# md_ver10_7.net
KiCad netlist of a schematic drawn in EAGLE
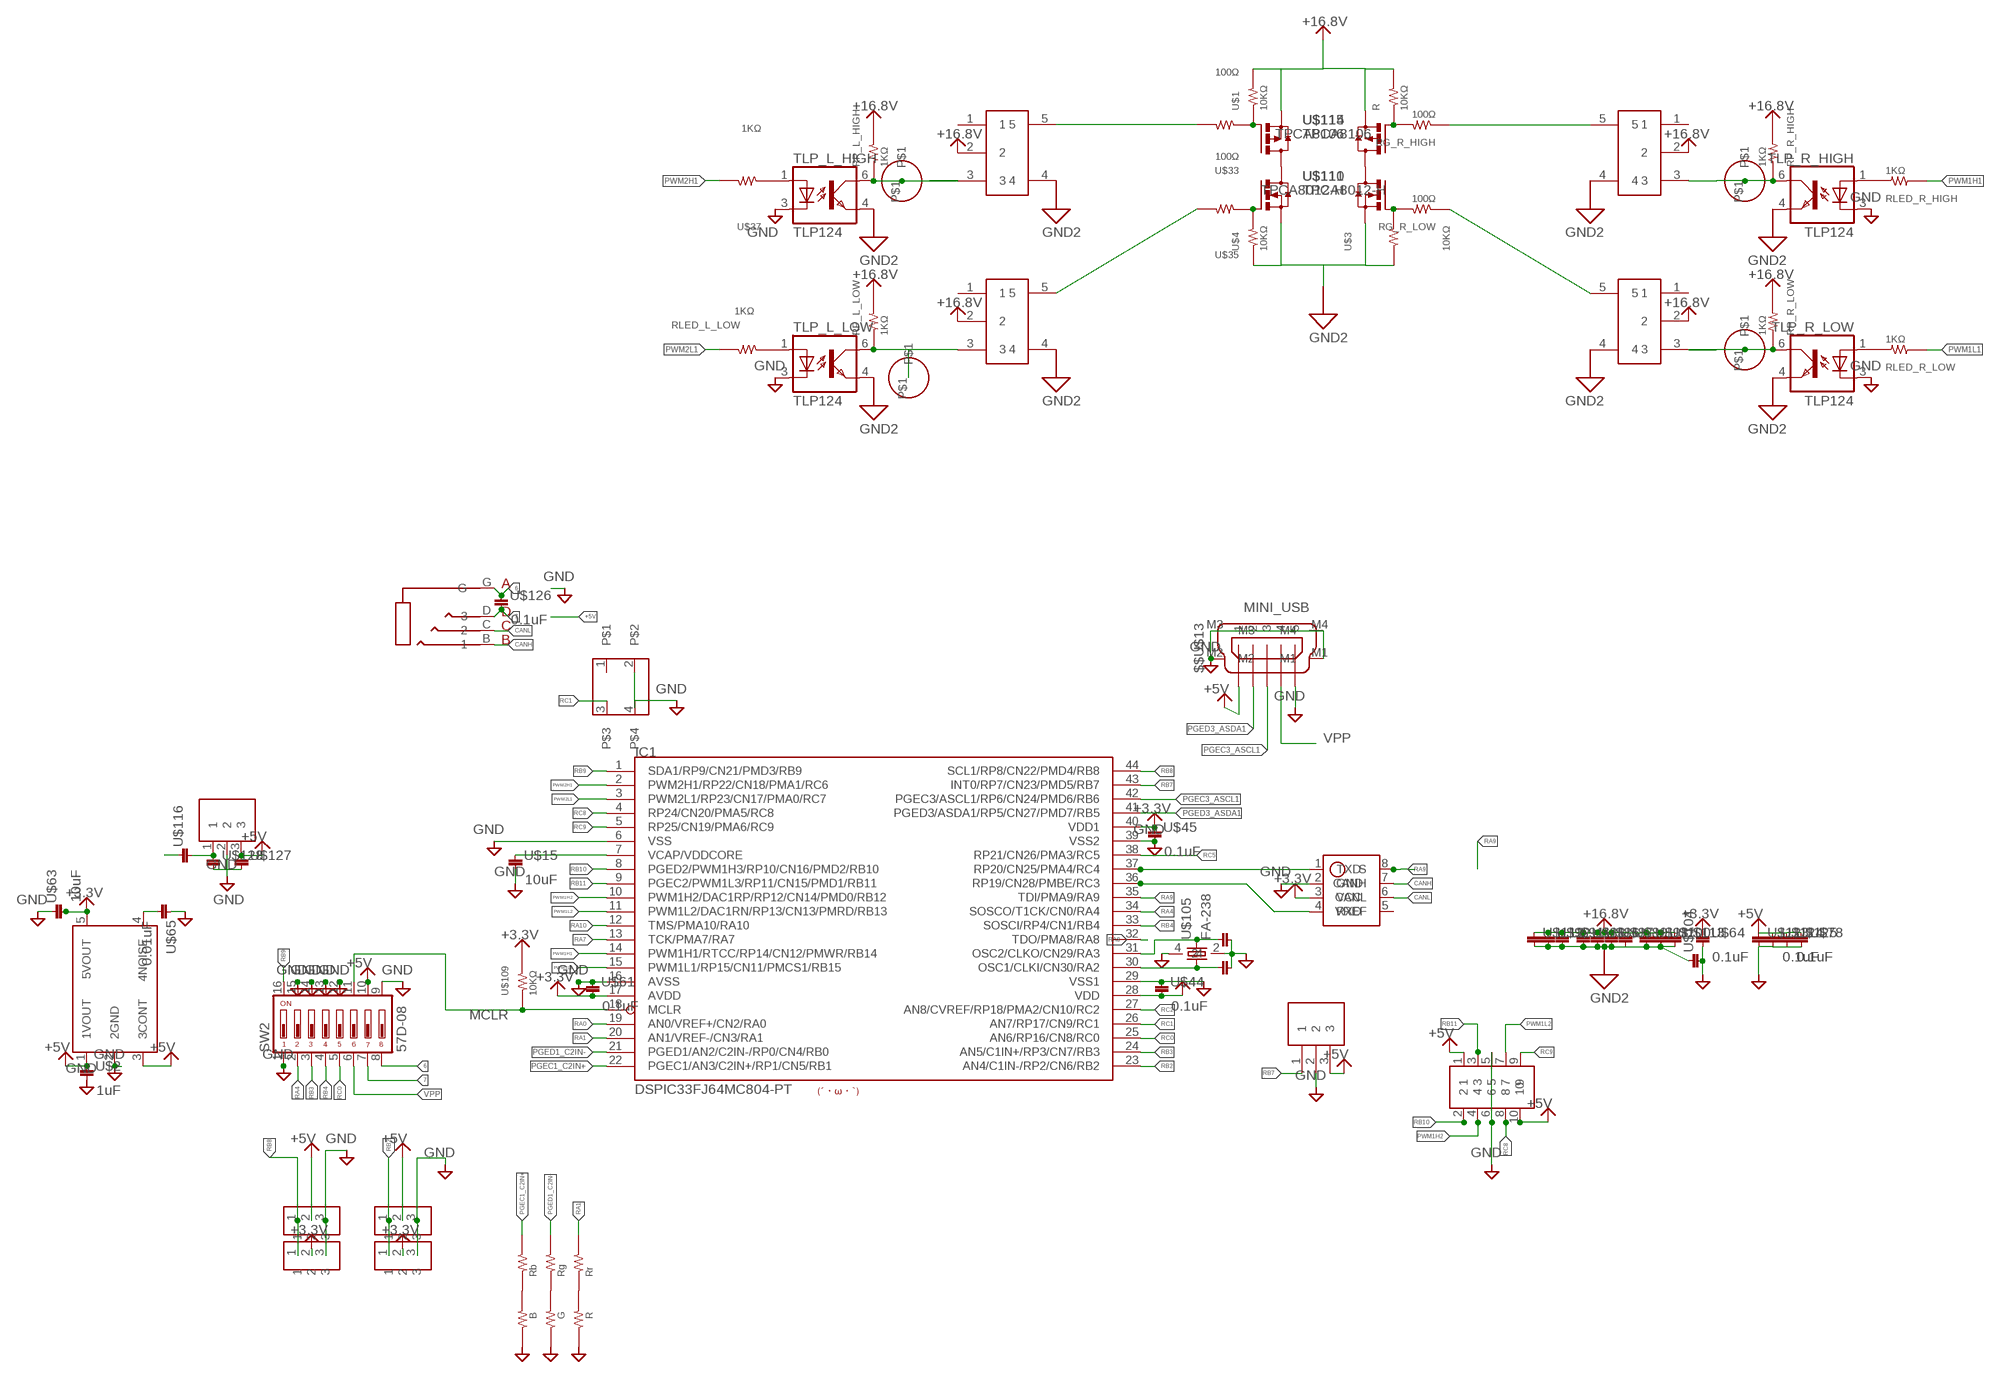
[diagram p0: schematic, sheet 1]

(export (version "E")
  (design (tool "Eeschema 10.0.6"))
  (components
    (comp (ref "$$U$5")
      (value "PAD1_4MM")
      (footprint "eagle-import:PAD1_4MM")
      (libsource (lib "eagle-import") (part "PAD1_4MM"))
    )
    (comp (ref "$$U$6")
      (value "PAD1_4MM")
      (footprint "eagle-import:PAD1_4MM")
      (libsource (lib "eagle-import") (part "PAD1_4MM"))
    )
    (comp (ref "$$U$13")
      (value "MINI_USB")
      (footprint "eagle-import:MINI_USB")
      (libsource (lib "eagle-import") (part "MINI_USB"))
    )
    (comp (ref "$$U$14")
      (value "AUDIO4")
      (footprint "eagle-import:AUDIO4_MJ")
      (libsource (lib "eagle-import") (part "AUDIO4"))
    )
    (comp (ref "$$U$102")
      (value "1608")
      (footprint "eagle-import:1608")
      (libsource (lib "eagle-import") (part "1608"))
    )
    (comp (ref "$$U$108")
      (value "Rr")
      (footprint "eagle-import:1608")
      (libsource (lib "eagle-import") (part "RESISTOR__SMD"))
    )
    (comp (ref "IC1")
      (value "DSPIC33FJ64MC804-PT")
      (footprint "eagle-import:TQFP44")
      (libsource (lib "eagle-import") (part "DSPIC33FJ64MC804-PT"))
    )
    (comp (ref "IC2")
      (value "TAR5SB")
      (footprint "eagle-import:SSOP5-P-0.95")
      (libsource (lib "eagle-import") (part "TAR5SB"))
    )
    (comp (ref "IC3")
      (value "SN65HVD1050")
      (footprint "eagle-import:SOIC8")
      (libsource (lib "eagle-import") (part "SN65HVD1050"))
    )
    (comp (ref "IC4")
      (value "ＰＬ－ＩＲＭ")
      (footprint "eagle-import:ＰＬ－ＩＲＭ")
      (libsource (lib "eagle-import") (part "ＰＬ－ＩＲＭ"))
    )
    (comp (ref "IC5")
      (value "Ｒ－７８Ｅ５．０")
      (footprint "eagle-import:Ｒ－７８Ｅ５．０")
      (libsource (lib "eagle-import") (part "Ｒ－７８Ｅ５．０"))
    )
    (comp (ref "IC_L_HIGH")
      (value "MCP1415")
      (footprint "eagle-import:SOT23-5L")
      (libsource (lib "eagle-import") (part "MCP1415"))
    )
    (comp (ref "IC_L_LOW")
      (value "MCP1415")
      (footprint "eagle-import:SOT23-5L")
      (libsource (lib "eagle-import") (part "MCP1415"))
    )
    (comp (ref "IC_R_HIGH")
      (value "MCP1415")
      (footprint "eagle-import:SOT23-5L")
      (libsource (lib "eagle-import") (part "MCP1415"))
    )
    (comp (ref "IC_R_LOW")
      (value "MCP1415")
      (footprint "eagle-import:SOT23-5L")
      (libsource (lib "eagle-import") (part "MCP1415"))
    )
    (comp (ref "R")
      (value "10KΩ")
      (footprint "eagle-import:1608")
      (libsource (lib "eagle-import") (part "RESISTOR__SMD"))
    )
    (comp (ref "RG_R_HIGH")
      (value "100Ω")
      (footprint "eagle-import:1608")
      (libsource (lib "eagle-import") (part "RESISTOR__SMD"))
    )
    (comp (ref "RG_R_LOW")
      (value "100Ω")
      (footprint "eagle-import:1608")
      (libsource (lib "eagle-import") (part "RESISTOR__SMD"))
    )
    (comp (ref "RLED_L_LOW")
      (value "1KΩ")
      (footprint "eagle-import:1608")
      (libsource (lib "eagle-import") (part "RESISTOR__SMD"))
    )
    (comp (ref "RLED_R_HIGH")
      (value "1KΩ")
      (footprint "eagle-import:1608")
      (libsource (lib "eagle-import") (part "RESISTOR__SMD"))
    )
    (comp (ref "RLED_R_LOW")
      (value "1KΩ")
      (footprint "eagle-import:1608")
      (libsource (lib "eagle-import") (part "RESISTOR__SMD"))
    )
    (comp (ref "RP_L_HIGH")
      (value "1KΩ")
      (footprint "eagle-import:1608")
      (libsource (lib "eagle-import") (part "RESISTOR__SMD"))
    )
    (comp (ref "RP_L_LOW")
      (value "1KΩ")
      (footprint "eagle-import:1608")
      (libsource (lib "eagle-import") (part "RESISTOR__SMD"))
    )
    (comp (ref "RP_R_HIGH")
      (value "1KΩ")
      (footprint "eagle-import:1608")
      (libsource (lib "eagle-import") (part "RESISTOR__SMD"))
    )
    (comp (ref "RP_R_LOW")
      (value "1KΩ")
      (footprint "eagle-import:1608")
      (libsource (lib "eagle-import") (part "RESISTOR__SMD"))
    )
    (comp (ref "SW1")
      (value "TACT")
      (footprint "eagle-import:TL1105")
      (libsource (lib "eagle-import") (part "TACT"))
    )
    (comp (ref "SW2")
      (value "57D-08")
      (footprint "eagle-import:57D")
      (libsource (lib "eagle-import") (part "57D-08"))
    )
    (comp (ref "TLP_L_HIGH")
      (value "TLP124")
      (footprint "eagle-import:11−4C1")
      (libsource (lib "eagle-import") (part "TLP124"))
    )
    (comp (ref "TLP_L_LOW")
      (value "TLP124")
      (footprint "eagle-import:11−4C1")
      (libsource (lib "eagle-import") (part "TLP124"))
    )
    (comp (ref "TLP_R_HIGH")
      (value "TLP124")
      (footprint "eagle-import:11−4C1")
      (libsource (lib "eagle-import") (part "TLP124"))
    )
    (comp (ref "TLP_R_LOW")
      (value "TLP124")
      (footprint "eagle-import:11−4C1")
      (libsource (lib "eagle-import") (part "TLP124"))
    )
    (comp (ref "U$1")
      (value "10KΩ")
      (footprint "eagle-import:1608")
      (libsource (lib "eagle-import") (part "RESISTOR__SMD"))
    )
    (comp (ref "U$2")
      (value "1uF")
      (footprint "eagle-import:1608")
      (libsource (lib "eagle-import") (part "1608"))
    )
    (comp (ref "U$3")
      (value "10KΩ")
      (footprint "eagle-import:1608")
      (libsource (lib "eagle-import") (part "RESISTOR__SMD"))
    )
    (comp (ref "U$4")
      (value "10KΩ")
      (footprint "eagle-import:1608")
      (libsource (lib "eagle-import") (part "RESISTOR__SMD"))
    )
    (comp (ref "U$7")
      (value "PAD1_4MM")
      (footprint "eagle-import:PAD1_4MM")
      (libsource (lib "eagle-import") (part "PAD1_4MM"))
    )
    (comp (ref "U$8")
      (value "PAD1_4MM")
      (footprint "eagle-import:PAD1_4MM")
      (libsource (lib "eagle-import") (part "PAD1_4MM"))
    )
    (comp (ref "U$9")
      (value "PIN_HEADER_52")
      (footprint "eagle-import:PIN_HEADER_5_2")
      (libsource (lib "eagle-import") (part "PIN_HEADER_52"))
    )
    (comp (ref "U$10")
      (value "R")
      (footprint "eagle-import:1608")
      (libsource (lib "eagle-import") (part "RESISTOR__SMD"))
    )
    (comp (ref "U$11")
      (value "G")
      (footprint "eagle-import:1608")
      (libsource (lib "eagle-import") (part "RESISTOR__SMD"))
    )
    (comp (ref "U$12")
      (value "B")
      (footprint "eagle-import:1608")
      (libsource (lib "eagle-import") (part "RESISTOR__SMD"))
    )
    (comp (ref "U$15")
      (value "10uF")
      (footprint "eagle-import:2012")
      (libsource (lib "eagle-import") (part "2012"))
    )
    (comp (ref "U$33")
      (value "100Ω")
      (footprint "eagle-import:1608")
      (libsource (lib "eagle-import") (part "RESISTOR__SMD"))
    )
    (comp (ref "U$35")
      (value "100Ω")
      (footprint "eagle-import:1608")
      (libsource (lib "eagle-import") (part "RESISTOR__SMD"))
    )
    (comp (ref "U$37")
      (value "1KΩ")
      (footprint "eagle-import:1608")
      (libsource (lib "eagle-import") (part "RESISTOR__SMD"))
    )
    (comp (ref "U$44")
      (value "0.1uF")
      (footprint "eagle-import:1608")
      (libsource (lib "eagle-import") (part "1608"))
    )
    (comp (ref "U$45")
      (value "0.1uF")
      (footprint "eagle-import:1608")
      (libsource (lib "eagle-import") (part "1608"))
    )
    (comp (ref "U$61")
      (value "0.1uF")
      (footprint "eagle-import:1608")
      (libsource (lib "eagle-import") (part "1608"))
    )
    (comp (ref "U$63")
      (value "10uF")
      (footprint "eagle-import:2012")
      (libsource (lib "eagle-import") (part "2012"))
    )
    (comp (ref "U$64")
      (value "0.1uF")
      (footprint "eagle-import:1608")
      (libsource (lib "eagle-import") (part "1608"))
    )
    (comp (ref "U$65")
      (value "0.01uF")
      (footprint "eagle-import:1608")
      (libsource (lib "eagle-import") (part "1608"))
    )
    (comp (ref "U$69")
      (value "3PIN_HALF")
      (footprint "eagle-import:3PIN_INT_HALF")
      (libsource (lib "eagle-import") (part "3PIN_HALF"))
    )
    (comp (ref "U$75")
      (value "3PIN_HALF")
      (footprint "eagle-import:3PIN_INT_HALF")
      (libsource (lib "eagle-import") (part "3PIN_HALF"))
    )
    (comp (ref "U$78")
      (value "1608")
      (footprint "eagle-import:1608")
      (libsource (lib "eagle-import") (part "1608"))
    )
    (comp (ref "U$86")
      (value "3225")
      (footprint "eagle-import:3225")
      (libsource (lib "eagle-import") (part "3225"))
    )
    (comp (ref "U$87")
      (value "3225")
      (footprint "eagle-import:3225")
      (libsource (lib "eagle-import") (part "3225"))
    )
    (comp (ref "U$88")
      (value "3225")
      (footprint "eagle-import:3225")
      (libsource (lib "eagle-import") (part "3225"))
    )
    (comp (ref "U$89")
      (value "3225")
      (footprint "eagle-import:3225")
      (libsource (lib "eagle-import") (part "3225"))
    )
    (comp (ref "U$91")
      (value "1608")
      (footprint "eagle-import:1608")
      (libsource (lib "eagle-import") (part "1608"))
    )
    (comp (ref "U$92")
      (value "1608")
      (footprint "eagle-import:1608")
      (libsource (lib "eagle-import") (part "1608"))
    )
    (comp (ref "U$93")
      (value "1608")
      (footprint "eagle-import:1608")
      (libsource (lib "eagle-import") (part "1608"))
    )
    (comp (ref "U$100")
      (value "1608")
      (footprint "eagle-import:1608")
      (libsource (lib "eagle-import") (part "1608"))
    )
    (comp (ref "U$103")
      (value "1608")
      (footprint "eagle-import:1608")
      (libsource (lib "eagle-import") (part "1608"))
    )
    (comp (ref "U$104")
      (value "2012")
      (footprint "eagle-import:2012")
      (libsource (lib "eagle-import") (part "2012"))
    )
    (comp (ref "U$105")
      (value "FA-238")
      (footprint "eagle-import:FA-238")
      (libsource (lib "eagle-import") (part "FA-238"))
    )
    (comp (ref "U$106")
      (value "Rb")
      (footprint "eagle-import:1608")
      (libsource (lib "eagle-import") (part "RESISTOR__SMD"))
    )
    (comp (ref "U$107")
      (value "Rg")
      (footprint "eagle-import:1608")
      (libsource (lib "eagle-import") (part "RESISTOR__SMD"))
    )
    (comp (ref "U$109")
      (value "10KΩ")
      (footprint "eagle-import:1608")
      (libsource (lib "eagle-import") (part "RESISTOR__SMD"))
    )
    (comp (ref "U$110")
      (value "TPCA8012-H")
      (footprint "eagle-import:2-5Q1A")
      (libsource (lib "eagle-import") (part "TPCA8012-H"))
    )
    (comp (ref "U$111")
      (value "TPCA8012-H")
      (footprint "eagle-import:2-5Q1A")
      (libsource (lib "eagle-import") (part "TPCA8012-H"))
    )
    (comp (ref "U$112")
      (value "1608")
      (footprint "eagle-import:1608")
      (libsource (lib "eagle-import") (part "1608"))
    )
    (comp (ref "U$113")
      (value "1608")
      (footprint "eagle-import:1608")
      (libsource (lib "eagle-import") (part "1608"))
    )
    (comp (ref "U$114")
      (value "TPCA8106")
      (footprint "eagle-import:2-5Q1A")
      (libsource (lib "eagle-import") (part "TPCA8106"))
    )
    (comp (ref "U$115")
      (value "TPCA8106")
      (footprint "eagle-import:2-5Q1A")
      (libsource (lib "eagle-import") (part "TPCA8106"))
    )
    (comp (ref "U$116")
      (value "2012")
      (footprint "eagle-import:2012")
      (libsource (lib "eagle-import") (part "2012"))
    )
    (comp (ref "U$117")
      (value "3PIN_HALF")
      (footprint "eagle-import:3PIN_INT_HALF")
      (libsource (lib "eagle-import") (part "3PIN_HALF"))
    )
    (comp (ref "U$118")
      (value "3PIN_HALF")
      (footprint "eagle-import:3PIN_INT_HALF")
      (libsource (lib "eagle-import") (part "3PIN_HALF"))
    )
    (comp (ref "U$123")
      (value "1608")
      (footprint "eagle-import:1608")
      (libsource (lib "eagle-import") (part "1608"))
    )
    (comp (ref "U$124")
      (value "0.1uF")
      (footprint "eagle-import:1608")
      (libsource (lib "eagle-import") (part "1608"))
    )
    (comp (ref "U$125")
      (value "0.1uF")
      (footprint "eagle-import:1608")
      (libsource (lib "eagle-import") (part "1608"))
    )
    (comp (ref "U$126")
      (value "0.1uF")
      (footprint "eagle-import:1608")
      (libsource (lib "eagle-import") (part "1608"))
    )
    (comp (ref "U$127")
      (value "3216")
      (footprint "eagle-import:3216")
      (libsource (lib "eagle-import") (part "3216"))
    )
    (comp (ref "U$128")
      (value "1608")
      (footprint "eagle-import:1608")
      (libsource (lib "eagle-import") (part "1608"))
    )
    (comp (ref "U$129")
      (value "ROGO_SYOBON")
      (footprint "eagle-import:ROGO_SYOBON")
      (libsource (lib "eagle-import") (part "ROGO_SYOBON"))
    )
  )
  (nets
    (net (code "1") (name "+3.3V") (class "Default")
      (node (ref "IC1") (pin "17") (pinfunction "AVDD_17") (pintype "power_in"))
      (node (ref "IC1") (pin "28") (pinfunction "VDD_28") (pintype "power_in"))
      (node (ref "IC1") (pin "40") (pinfunction "VDD1_40") (pintype "power_in"))
      (node (ref "IC2") (pin "5") (pinfunction "5VOUT_5") (pintype "bidirectional"))
      (node (ref "IC3") (pin "3") (pinfunction "VCC_3") (pintype "bidirectional"))
      (node (ref "U$109") (pin "2") (pinfunction "P$2_2") (pintype "passive"))
      (node (ref "U$44") (pin "P$2") (pinfunction "2_P$2") (pintype "passive"))
      (node (ref "U$45") (pin "P$1") (pinfunction "1_P$1") (pintype "passive"))
      (node (ref "U$61") (pin "P$2") (pinfunction "2_P$2") (pintype "passive"))
      (node (ref "U$63") (pin "2") (pinfunction "2_2") (pintype "passive"))
      (node (ref "U$64") (pin "P$1") (pinfunction "1_P$1") (pintype "passive"))
      (node (ref "U$69") (pin "2") (pinfunction "2_2") (pintype "bidirectional"))
      (node (ref "U$75") (pin "2") (pinfunction "2_2") (pintype "bidirectional"))
    )
    (net (code "2") (name "+5V") (class "Default")
      (node (ref "$$U$13") (pin "1") (pinfunction "1_1") (pintype "input"))
      (node (ref "IC2") (pin "1") (pinfunction "1VOUT_1") (pintype "bidirectional"))
      (node (ref "IC2") (pin "3") (pinfunction "3CONT_3") (pintype "bidirectional"))
      (node (ref "IC4") (pin "3") (pinfunction "3_3") (pintype "bidirectional"))
      (node (ref "IC5") (pin "3") (pinfunction "3_3") (pintype "bidirectional"))
      (node (ref "SW2") (pin "10") (pinfunction "10_10") (pintype "passive"))
      (node (ref "U$117") (pin "2") (pinfunction "2_2") (pintype "bidirectional"))
      (node (ref "U$118") (pin "2") (pinfunction "2_2") (pintype "bidirectional"))
      (node (ref "U$123") (pin "P$1") (pinfunction "1_P$1") (pintype "passive"))
      (node (ref "U$124") (pin "P$1") (pinfunction "1_P$1") (pintype "passive"))
      (node (ref "U$125") (pin "P$1") (pinfunction "1_P$1") (pintype "passive"))
      (node (ref "U$127") (pin "P$1") (pinfunction "1_P$1") (pintype "passive"))
      (node (ref "U$2") (pin "P$1") (pinfunction "1_P$1") (pintype "passive"))
      (node (ref "U$78") (pin "P$1") (pinfunction "1_P$1") (pintype "passive"))
      (node (ref "U$9") (pin "1") (pinfunction "1_1") (pintype "bidirectional"))
      (node (ref "U$9") (pin "10") (pinfunction "10_10") (pintype "bidirectional"))
    )
    (net (code "3") (name "+16.8V") (class "Default")
      (node (ref "IC_L_HIGH") (pin "2") (pinfunction "2_2") (pintype "bidirectional"))
      (node (ref "IC_L_LOW") (pin "2") (pinfunction "2_2") (pintype "bidirectional"))
      (node (ref "IC_R_HIGH") (pin "2") (pinfunction "2_2") (pintype "bidirectional"))
      (node (ref "IC_R_LOW") (pin "2") (pinfunction "2_2") (pintype "bidirectional"))
      (node (ref "R") (pin "2") (pinfunction "P$2_2") (pintype "passive"))
      (node (ref "RP_L_HIGH") (pin "2") (pinfunction "P$2_2") (pintype "passive"))
      (node (ref "RP_L_LOW") (pin "2") (pinfunction "P$2_2") (pintype "passive"))
      (node (ref "RP_R_HIGH") (pin "2") (pinfunction "P$2_2") (pintype "passive"))
      (node (ref "RP_R_LOW") (pin "2") (pinfunction "P$2_2") (pintype "passive"))
      (node (ref "U$1") (pin "2") (pinfunction "P$2_2") (pintype "passive"))
      (node (ref "U$100") (pin "P$1") (pinfunction "1_P$1") (pintype "passive"))
      (node (ref "U$112") (pin "P$1") (pinfunction "1_P$1") (pintype "passive"))
      (node (ref "U$113") (pin "P$1") (pinfunction "1_P$1") (pintype "passive"))
      (node (ref "U$114") (pin "1") (pinfunction "S_1") (pintype "passive"))
      (node (ref "U$114") (pin "2") (pinfunction "S_2") (pintype "passive"))
      (node (ref "U$114") (pin "3") (pinfunction "S_3") (pintype "passive"))
      (node (ref "U$115") (pin "1") (pinfunction "S_1") (pintype "passive"))
      (node (ref "U$115") (pin "2") (pinfunction "S_2") (pintype "passive"))
      (node (ref "U$115") (pin "3") (pinfunction "S_3") (pintype "passive"))
      (node (ref "U$86") (pin "P$1") (pinfunction "1_P$1") (pintype "passive"))
      (node (ref "U$87") (pin "P$1") (pinfunction "1_P$1") (pintype "passive"))
      (node (ref "U$88") (pin "P$1") (pinfunction "1_P$1") (pintype "passive"))
      (node (ref "U$89") (pin "P$1") (pinfunction "1_P$1") (pintype "passive"))
      (node (ref "U$91") (pin "P$1") (pinfunction "1_P$1") (pintype "passive"))
      (node (ref "U$92") (pin "P$1") (pinfunction "1_P$1") (pintype "passive"))
      (node (ref "U$93") (pin "P$1") (pinfunction "1_P$1") (pintype "passive"))
    )
    (net (code "4") (name "/MCLR") (class "Default")
      (node (ref "IC1") (pin "18") (pinfunction "MCLR_18") (pintype "input"))
      (node (ref "SW2") (pin "11") (pinfunction "11_11") (pintype "passive"))
      (node (ref "U$109") (pin "1") (pinfunction "P$1_1") (pintype "passive"))
    )
    (net (code "5") (name "6") (class "Default")
      (node (ref "$$U$14") (pin "G") (pinfunction "G_G") (pintype "bidirectional"))
      (node (ref "SW2") (pin "8") (pinfunction "8_8") (pintype "passive"))
      (node (ref "U$126") (pin "P$1") (pinfunction "1_P$1") (pintype "passive"))
    )
    (net (code "6") (name "7") (class "Default")
      (node (ref "$$U$14") (pin "D") (pinfunction "3_D") (pintype "bidirectional"))
      (node (ref "SW2") (pin "7") (pinfunction "7_7") (pintype "passive"))
      (node (ref "U$126") (pin "P$2") (pinfunction "2_P$2") (pintype "passive"))
    )
    (net (code "7") (name "CANH") (class "Default")
      (node (ref "$$U$14") (pin "B") (pinfunction "1_B") (pintype "bidirectional"))
      (node (ref "IC3") (pin "7") (pinfunction "CANH_7") (pintype "bidirectional"))
    )
    (net (code "8") (name "CANL") (class "Default")
      (node (ref "$$U$14") (pin "C") (pinfunction "2_C") (pintype "bidirectional"))
      (node (ref "IC3") (pin "6") (pinfunction "CANL_6") (pintype "bidirectional"))
    )
    (net (code "9") (name "GND") (class "Default")
      (node (ref "$$U$102") (pin "P$2") (pinfunction "2_P$2") (pintype "passive"))
      (node (ref "$$U$13") (pin "5") (pinfunction "5_5") (pintype "input"))
      (node (ref "$$U$13") (pin "M1") (pinfunction "M1_M1") (pintype "bidirectional"))
      (node (ref "$$U$13") (pin "M2") (pinfunction "M2_M2") (pintype "bidirectional"))
      (node (ref "$$U$13") (pin "M3") (pinfunction "M3_M3") (pintype "bidirectional"))
      (node (ref "$$U$13") (pin "M4") (pinfunction "M4_M4") (pintype "bidirectional"))
      (node (ref "IC1") (pin "16") (pinfunction "AVSS_16") (pintype "power_in"))
      (node (ref "IC1") (pin "29") (pinfunction "VSS1_29") (pintype "power_in"))
      (node (ref "IC1") (pin "39") (pinfunction "VSS2_39") (pintype "power_in"))
      (node (ref "IC1") (pin "6") (pinfunction "VSS_6") (pintype "power_in"))
      (node (ref "IC2") (pin "2") (pinfunction "2GND_2") (pintype "bidirectional"))
      (node (ref "IC3") (pin "2") (pinfunction "GND_2") (pintype "bidirectional"))
      (node (ref "IC4") (pin "2") (pinfunction "2_2") (pintype "bidirectional"))
      (node (ref "IC5") (pin "2") (pinfunction "2_2") (pintype "bidirectional"))
      (node (ref "SW1") (pin "2") (pinfunction "P$2_2") (pintype "bidirectional"))
      (node (ref "SW1") (pin "4") (pinfunction "P$4_4") (pintype "bidirectional"))
      (node (ref "SW2") (pin "1") (pinfunction "1_1") (pintype "passive"))
      (node (ref "SW2") (pin "12") (pinfunction "12_12") (pintype "passive"))
      (node (ref "SW2") (pin "13") (pinfunction "13_13") (pintype "passive"))
      (node (ref "SW2") (pin "14") (pinfunction "14_14") (pintype "passive"))
      (node (ref "SW2") (pin "15") (pinfunction "15_15") (pintype "passive"))
      (node (ref "SW2") (pin "9") (pinfunction "9_9") (pintype "passive"))
      (node (ref "TLP_L_HIGH") (pin "3") (pinfunction "C_3") (pintype "passive"))
      (node (ref "TLP_L_LOW") (pin "3") (pinfunction "C_3") (pintype "passive"))
      (node (ref "TLP_R_HIGH") (pin "3") (pinfunction "C_3") (pintype "passive"))
      (node (ref "TLP_R_LOW") (pin "3") (pinfunction "C_3") (pintype "passive"))
      (node (ref "U$10") (pin "1") (pinfunction "P$1_1") (pintype "passive"))
      (node (ref "U$103") (pin "P$2") (pinfunction "2_P$2") (pintype "passive"))
      (node (ref "U$104") (pin "2") (pinfunction "2_2") (pintype "passive"))
      (node (ref "U$105") (pin "2") (pinfunction "2_2") (pintype "bidirectional"))
      (node (ref "U$105") (pin "4") (pinfunction "4_4") (pintype "bidirectional"))
      (node (ref "U$11") (pin "1") (pinfunction "P$1_1") (pintype "passive"))
      (node (ref "U$117") (pin "3") (pinfunction "3_3") (pintype "bidirectional"))
      (node (ref "U$118") (pin "3") (pinfunction "3_3") (pintype "bidirectional"))
      (node (ref "U$12") (pin "1") (pinfunction "P$1_1") (pintype "passive"))
      (node (ref "U$123") (pin "P$2") (pinfunction "2_P$2") (pintype "passive"))
      (node (ref "U$124") (pin "P$2") (pinfunction "2_P$2") (pintype "passive"))
      (node (ref "U$125") (pin "P$2") (pinfunction "2_P$2") (pintype "passive"))
      (node (ref "U$127") (pin "P$2") (pinfunction "2_P$2") (pintype "passive"))
      (node (ref "U$128") (pin "P$2") (pinfunction "2_P$2") (pintype "passive"))
      (node (ref "U$15") (pin "2") (pinfunction "2_2") (pintype "passive"))
      (node (ref "U$2") (pin "P$2") (pinfunction "2_P$2") (pintype "passive"))
      (node (ref "U$44") (pin "P$1") (pinfunction "1_P$1") (pintype "passive"))
      (node (ref "U$45") (pin "P$2") (pinfunction "2_P$2") (pintype "passive"))
      (node (ref "U$61") (pin "P$1") (pinfunction "1_P$1") (pintype "passive"))
      (node (ref "U$63") (pin "1") (pinfunction "1_1") (pintype "passive"))
      (node (ref "U$64") (pin "P$2") (pinfunction "2_P$2") (pintype "passive"))
      (node (ref "U$65") (pin "P$1") (pinfunction "1_P$1") (pintype "passive"))
      (node (ref "U$69") (pin "3") (pinfunction "3_3") (pintype "bidirectional"))
      (node (ref "U$75") (pin "3") (pinfunction "3_3") (pintype "bidirectional"))
      (node (ref "U$78") (pin "P$2") (pinfunction "2_P$2") (pintype "passive"))
      (node (ref "U$9") (pin "5") (pinfunction "5_5") (pintype "bidirectional"))
      (node (ref "U$9") (pin "6") (pinfunction "6_6") (pintype "bidirectional"))
    )
    (net (code "10") (name "GND2") (class "Default")
      (node (ref "IC_L_HIGH") (pin "4") (pinfunction "4_4") (pintype "bidirectional"))
      (node (ref "IC_L_LOW") (pin "4") (pinfunction "4_4") (pintype "bidirectional"))
      (node (ref "IC_R_HIGH") (pin "4") (pinfunction "4_4") (pintype "bidirectional"))
      (node (ref "IC_R_LOW") (pin "4") (pinfunction "4_4") (pintype "bidirectional"))
      (node (ref "TLP_L_HIGH") (pin "4") (pinfunction "EMIT_4") (pintype "passive"))
      (node (ref "TLP_L_LOW") (pin "4") (pinfunction "EMIT_4") (pintype "passive"))
      (node (ref "TLP_R_HIGH") (pin "4") (pinfunction "EMIT_4") (pintype "passive"))
      (node (ref "TLP_R_LOW") (pin "4") (pinfunction "EMIT_4") (pintype "passive"))
      (node (ref "U$100") (pin "P$2") (pinfunction "2_P$2") (pintype "passive"))
      (node (ref "U$104") (pin "1") (pinfunction "1_1") (pintype "passive"))
      (node (ref "U$110") (pin "1") (pinfunction "S_1") (pintype "passive"))
      (node (ref "U$110") (pin "2") (pinfunction "S_2") (pintype "passive"))
      (node (ref "U$110") (pin "3") (pinfunction "S_3") (pintype "passive"))
      (node (ref "U$111") (pin "1") (pinfunction "S_1") (pintype "passive"))
      (node (ref "U$111") (pin "2") (pinfunction "S_2") (pintype "passive"))
      (node (ref "U$111") (pin "3") (pinfunction "S_3") (pintype "passive"))
      (node (ref "U$112") (pin "P$2") (pinfunction "2_P$2") (pintype "passive"))
      (node (ref "U$113") (pin "P$2") (pinfunction "2_P$2") (pintype "passive"))
      (node (ref "U$3") (pin "1") (pinfunction "P$1_1") (pintype "passive"))
      (node (ref "U$4") (pin "1") (pinfunction "P$1_1") (pintype "passive"))
      (node (ref "U$86") (pin "P$2") (pinfunction "2_P$2") (pintype "passive"))
      (node (ref "U$87") (pin "P$2") (pinfunction "2_P$2") (pintype "passive"))
      (node (ref "U$88") (pin "P$2") (pinfunction "2_P$2") (pintype "passive"))
      (node (ref "U$89") (pin "P$2") (pinfunction "2_P$2") (pintype "passive"))
      (node (ref "U$91") (pin "P$2") (pinfunction "2_P$2") (pintype "passive"))
      (node (ref "U$92") (pin "P$2") (pinfunction "2_P$2") (pintype "passive"))
      (node (ref "U$93") (pin "P$2") (pinfunction "2_P$2") (pintype "passive"))
    )
    (net (code "11") (name "Net-($$U$102-1)") (class "Default")
      (node (ref "$$U$102") (pin "P$1") (pinfunction "1_P$1") (pintype "passive"))
      (node (ref "IC1") (pin "30") (pinfunction "OSC1/CLKI/CN30/RA2_30") (pintype "bidirectional"))
      (node (ref "U$105") (pin "1") (pinfunction "1_1") (pintype "passive"))
    )
    (net (code "12") (name "Net-($$U$108-P$1)") (class "Default")
      (node (ref "$$U$108") (pin "1") (pinfunction "P$1_1") (pintype "passive"))
      (node (ref "U$10") (pin "2") (pinfunction "P$2_2") (pintype "passive"))
    )
    (net (code "13") (name "Net-(IC1-OSC2{slash}CLKO{slash}CN29{slash}RA3)") (class "Default")
      (node (ref "IC1") (pin "31") (pinfunction "OSC2/CLKO/CN29/RA3_31") (pintype "bidirectional"))
      (node (ref "U$103") (pin "P$1") (pinfunction "1_P$1") (pintype "passive"))
      (node (ref "U$105") (pin "3") (pinfunction "3_3") (pintype "passive"))
    )
    (net (code "14") (name "Net-(IC1-RP19{slash}CN28{slash}PMBE{slash}RC3)") (class "Default")
      (node (ref "IC1") (pin "36") (pinfunction "RP19/CN28/PMBE/RC3_36") (pintype "bidirectional"))
      (node (ref "IC3") (pin "4") (pinfunction "RXD_4") (pintype "bidirectional"))
    )
    (net (code "15") (name "Net-(IC1-RP20{slash}CN25{slash}PMA4{slash}RC4)") (class "Default")
      (node (ref "IC1") (pin "37") (pinfunction "RP20/CN25/PMA4/RC4_37") (pintype "bidirectional"))
      (node (ref "IC3") (pin "1") (pinfunction "TXD_1") (pintype "bidirectional"))
    )
    (net (code "16") (name "Net-(IC1-VCAP{slash}VDDCORE)") (class "Default")
      (node (ref "IC1") (pin "7") (pinfunction "VCAP/VDDCORE_7") (pintype "power_in"))
      (node (ref "U$15") (pin "1") (pinfunction "1_1") (pintype "passive"))
    )
    (net (code "17") (name "Net-(IC2-4NOISE)") (class "Default")
      (node (ref "IC2") (pin "4") (pinfunction "4NOISE_4") (pintype "bidirectional"))
      (node (ref "U$65") (pin "P$2") (pinfunction "2_P$2") (pintype "passive"))
    )
    (net (code "18") (name "Net-(R-P$1)") (class "Default")
      (node (ref "R") (pin "1") (pinfunction "P$1_1") (pintype "passive"))
      (node (ref "RG_R_HIGH") (pin "2") (pinfunction "P$2_2") (pintype "passive"))
      (node (ref "U$114") (pin "4") (pinfunction "G_4") (pintype "passive"))
    )
    (net (code "19") (name "Net-(RG_R_HIGH-P$1)") (class "Default")
      (node (ref "IC_R_HIGH") (pin "5") (pinfunction "5_5") (pintype "bidirectional"))
      (node (ref "RG_R_HIGH") (pin "1") (pinfunction "P$1_1") (pintype "passive"))
    )
    (net (code "20") (name "Net-(RG_R_LOW-P$1)") (class "Default")
      (node (ref "IC_R_LOW") (pin "5") (pinfunction "5_5") (pintype "bidirectional"))
      (node (ref "RG_R_LOW") (pin "1") (pinfunction "P$1_1") (pintype "passive"))
    )
    (net (code "21") (name "Net-(RG_R_LOW-P$2)") (class "Default")
      (node (ref "RG_R_LOW") (pin "2") (pinfunction "P$2_2") (pintype "passive"))
      (node (ref "U$110") (pin "4") (pinfunction "G_4") (pintype "passive"))
      (node (ref "U$3") (pin "2") (pinfunction "P$2_2") (pintype "passive"))
    )
    (net (code "22") (name "Net-(RLED_L_LOW-P$1)") (class "Default")
      (node (ref "RLED_L_LOW") (pin "1") (pinfunction "P$1_1") (pintype "passive"))
      (node (ref "TLP_L_LOW") (pin "1") (pinfunction "A_1") (pintype "passive"))
    )
    (net (code "23") (name "Net-(RLED_R_HIGH-P$1)") (class "Default")
      (node (ref "RLED_R_HIGH") (pin "1") (pinfunction "P$1_1") (pintype "passive"))
      (node (ref "TLP_R_HIGH") (pin "1") (pinfunction "A_1") (pintype "passive"))
    )
    (net (code "24") (name "Net-(RLED_R_LOW-P$1)") (class "Default")
      (node (ref "RLED_R_LOW") (pin "1") (pinfunction "P$1_1") (pintype "passive"))
      (node (ref "TLP_R_LOW") (pin "1") (pinfunction "A_1") (pintype "passive"))
    )
    (net (code "25") (name "Net-(RP_L_HIGH-P$1)") (class "Default")
      (node (ref "$$U$5") (pin "P$1") (pinfunction "P$1_P$1") (pintype "bidirectional"))
      (node (ref "IC_L_HIGH") (pin "3") (pinfunction "3_3") (pintype "bidirectional"))
      (node (ref "RP_L_HIGH") (pin "1") (pinfunction "P$1_1") (pintype "passive"))
      (node (ref "TLP_L_HIGH") (pin "6") (pinfunction "COL_6") (pintype "passive"))
    )
    (net (code "26") (name "Net-(RP_L_LOW-P$1)") (class "Default")
      (node (ref "$$U$6") (pin "P$1") (pinfunction "P$1_P$1") (pintype "bidirectional"))
      (node (ref "IC_L_LOW") (pin "3") (pinfunction "3_3") (pintype "bidirectional"))
      (node (ref "RP_L_LOW") (pin "1") (pinfunction "P$1_1") (pintype "passive"))
      (node (ref "TLP_L_LOW") (pin "6") (pinfunction "COL_6") (pintype "passive"))
    )
    (net (code "27") (name "Net-(RP_R_HIGH-P$1)") (class "Default")
      (node (ref "IC_R_HIGH") (pin "3") (pinfunction "3_3") (pintype "bidirectional"))
      (node (ref "RP_R_HIGH") (pin "1") (pinfunction "P$1_1") (pintype "passive"))
      (node (ref "TLP_R_HIGH") (pin "6") (pinfunction "COL_6") (pintype "passive"))
      (node (ref "U$8") (pin "P$1") (pinfunction "P$1_P$1") (pintype "bidirectional"))
    )
    (net (code "28") (name "Net-(RP_R_LOW-P$1)") (class "Default")
      (node (ref "IC_R_LOW") (pin "3") (pinfunction "3_3") (pintype "bidirectional"))
      (node (ref "RP_R_LOW") (pin "1") (pinfunction "P$1_1") (pintype "passive"))
      (node (ref "TLP_R_LOW") (pin "6") (pinfunction "COL_6") (pintype "passive"))
      (node (ref "U$7") (pin "P$1") (pinfunction "P$1_P$1") (pintype "bidirectional"))
    )
    (net (code "29") (name "Net-(TLP_L_HIGH-A)") (class "Default")
      (node (ref "TLP_L_HIGH") (pin "1") (pinfunction "A_1") (pintype "passive"))
      (node (ref "U$37") (pin "1") (pinfunction "P$1_1") (pintype "passive"))
    )
    (net (code "30") (name "Net-(U$1-P$1)") (class "Default")
      (node (ref "U$1") (pin "1") (pinfunction "P$1_1") (pintype "passive"))
      (node (ref "U$115") (pin "4") (pinfunction "G_4") (pintype "passive"))
      (node (ref "U$33") (pin "1") (pinfunction "P$1_1") (pintype "passive"))
    )
    (net (code "31") (name "Net-(U$33-P$2)") (class "Default")
      (node (ref "IC_L_HIGH") (pin "5") (pinfunction "5_5") (pintype "bidirectional"))
      (node (ref "U$33") (pin "2") (pinfunction "P$2_2") (pintype "passive"))
    )
    (net (code "32") (name "Net-(U$35-P$2)") (class "Default")
      (node (ref "IC_L_LOW") (pin "5") (pinfunction "5_5") (pintype "bidirectional"))
      (node (ref "U$35") (pin "2") (pinfunction "P$2_2") (pintype "passive"))
    )
    (net (code "33") (name "Net-(U$106-P$1)") (class "Default")
      (node (ref "U$106") (pin "1") (pinfunction "P$1_1") (pintype "passive"))
      (node (ref "U$12") (pin "2") (pinfunction "P$2_2") (pintype "passive"))
    )
    (net (code "34") (name "Net-(U$107-P$1)") (class "Default")
      (node (ref "U$107") (pin "1") (pinfunction "P$1_1") (pintype "passive"))
      (node (ref "U$11") (pin "2") (pinfunction "P$2_2") (pintype "passive"))
    )
    (net (code "35") (name "Net-(U$110-D-Pad5)") (class "Default")
      (node (ref "U$110") (pin "5") (pinfunction "D_5") (pintype "passive"))
      (node (ref "U$110") (pin "6") (pinfunction "D_6") (pintype "passive"))
      (node (ref "U$110") (pin "7") (pinfunction "D_7") (pintype "passive"))
      (node (ref "U$110") (pin "8") (pinfunction "D_8") (pintype "passive"))
      (node (ref "U$114") (pin "5") (pinfunction "D_5") (pintype "passive"))
      (node (ref "U$114") (pin "6") (pinfunction "D_6") (pintype "passive"))
      (node (ref "U$114") (pin "7") (pinfunction "D_7") (pintype "passive"))
      (node (ref "U$114") (pin "8") (pinfunction "D_8") (pintype "passive"))
    )
    (net (code "36") (name "Net-(U$111-D-Pad5)") (class "Default")
      (node (ref "U$111") (pin "5") (pinfunction "D_5") (pintype "passive"))
      (node (ref "U$111") (pin "6") (pinfunction "D_6") (pintype "passive"))
      (node (ref "U$111") (pin "7") (pinfunction "D_7") (pintype "passive"))
      (node (ref "U$111") (pin "8") (pinfunction "D_8") (pintype "passive"))
      (node (ref "U$115") (pin "5") (pinfunction "D_5") (pintype "passive"))
      (node (ref "U$115") (pin "6") (pinfunction "D_6") (pintype "passive"))
      (node (ref "U$115") (pin "7") (pinfunction "D_7") (pintype "passive"))
      (node (ref "U$115") (pin "8") (pinfunction "D_8") (pintype "passive"))
    )
    (net (code "37") (name "Net-(U$111-G)") (class "Default")
      (node (ref "U$111") (pin "4") (pinfunction "G_4") (pintype "passive"))
      (node (ref "U$35") (pin "1") (pinfunction "P$1_1") (pintype "passive"))
      (node (ref "U$4") (pin "2") (pinfunction "P$2_2") (pintype "passive"))
    )
    (net (code "38") (name "Net-(U$128-1)") (class "Default")
      (node (ref "IC5") (pin "1") (pinfunction "1_1") (pintype "bidirectional"))
      (node (ref "U$116") (pin "2") (pinfunction "2_2") (pintype "passive"))
      (node (ref "U$128") (pin "P$1") (pinfunction "1_P$1") (pintype "passive"))
    )
    (net (code "39") (name "PGEC1_C2IN+") (class "Default")
      (node (ref "IC1") (pin "22") (pinfunction "PGEC1/AN3/C2IN+/RP1/CN5/RB1_22") (pintype "bidirectional"))
      (node (ref "U$106") (pin "2") (pinfunction "P$2_2") (pintype "passive"))
    )
    (net (code "40") (name "PGEC3_ASCL1") (class "Default")
      (node (ref "$$U$13") (pin "3") (pinfunction "3_3") (pintype "input"))
      (node (ref "IC1") (pin "42") (pinfunction "PGEC3/ASCL1/RP6/CN24/PMD6/RB6_42") (pintype "bidirectional"))
    )
    (net (code "41") (name "PGED1_C2IN-") (class "Default")
      (node (ref "IC1") (pin "21") (pinfunction "PGED1/AN2/C2IN-/RP0/CN4/RB0_21") (pintype "bidirectional"))
      (node (ref "U$107") (pin "2") (pinfunction "P$2_2") (pintype "passive"))
    )
    (net (code "42") (name "PGED3_ASDA1") (class "Default")
      (node (ref "$$U$13") (pin "2") (pinfunction "2_2") (pintype "input"))
      (node (ref "IC1") (pin "41") (pinfunction "PGED3/ASDA1/RP5/CN27/PMD7/RB5_41") (pintype "bidirectional"))
    )
    (net (code "43") (name "PWM1H1") (class "Default")
      (node (ref "IC1") (pin "14") (pinfunction "PWM1H1/RTCC/RP14/CN12/PMWR/RB14_14") (pintype "bidirectional"))
      (node (ref "RLED_R_HIGH") (pin "2") (pinfunction "P$2_2") (pintype "passive"))
    )
    (net (code "44") (name "PWM1H2") (class "Default")
      (node (ref "IC1") (pin "10") (pinfunction "PWM1H2/DAC1RP/RP12/CN14/PMD0/RB12_10") (pintype "bidirectional"))
      (node (ref "U$9") (pin "4") (pinfunction "4_4") (pintype "bidirectional"))
    )
    (net (code "45") (name "PWM1L1") (class "Default")
      (node (ref "IC1") (pin "15") (pinfunction "PWM1L1/RP15/CN11/PMCS1/RB15_15") (pintype "bidirectional"))
      (node (ref "RLED_R_LOW") (pin "2") (pinfunction "P$2_2") (pintype "passive"))
    )
    (net (code "46") (name "PWM1L2") (class "Default")
      (node (ref "IC1") (pin "11") (pinfunction "PWM1L2/DAC1RN/RP13/CN13/PMRD/RB13_11") (pintype "bidirectional"))
      (node (ref "U$9") (pin "7") (pinfunction "7_7") (pintype "bidirectional"))
    )
    (net (code "47") (name "PWM2H1") (class "Default")
      (node (ref "IC1") (pin "2") (pinfunction "PWM2H1/RP22/CN18/PMA1/RC6_2") (pintype "bidirectional"))
      (node (ref "U$37") (pin "2") (pinfunction "P$2_2") (pintype "passive"))
    )
    (net (code "48") (name "PWM2L1") (class "Default")
      (node (ref "IC1") (pin "3") (pinfunction "PWM2L1/RP23/CN17/PMA0/RC7_3") (pintype "bidirectional"))
      (node (ref "RLED_L_LOW") (pin "2") (pinfunction "P$2_2") (pintype "passive"))
    )
    (net (code "49") (name "RA0") (class "Default")
      (node (ref "IC1") (pin "19") (pinfunction "AN0/VREF+/CN2/RA0_19") (pintype "bidirectional"))
    )
    (net (code "50") (name "RA1") (class "Default")
      (node (ref "$$U$108") (pin "2") (pinfunction "P$2_2") (pintype "passive"))
      (node (ref "IC1") (pin "20") (pinfunction "AN1/VREF-/CN3/RA1_20") (pintype "bidirectional"))
    )
    (net (code "51") (name "RA4") (class "Default")
      (node (ref "IC1") (pin "34") (pinfunction "SOSCO/T1CK/CN0/RA4_34") (pintype "bidirectional"))
      (node (ref "SW2") (pin "2") (pinfunction "2_2") (pintype "passive"))
    )
    (net (code "52") (name "RA7") (class "Default")
      (node (ref "IC1") (pin "13") (pinfunction "TCK/PMA7/RA7_13") (pintype "bidirectional"))
    )
    (net (code "53") (name "RA8") (class "Default")
      (node (ref "IC1") (pin "32") (pinfunction "TDO/PMA8/RA8_32") (pintype "bidirectional"))
    )
    (net (code "54") (name "RA9") (class "Default")
      (node (ref "IC1") (pin "35") (pinfunction "TDI/PMA9/RA9_35") (pintype "bidirectional"))
      (node (ref "IC3") (pin "8") (pinfunction "S_8") (pintype "bidirectional"))
    )
    (net (code "55") (name "RA10") (class "Default")
      (node (ref "IC1") (pin "12") (pinfunction "TMS/PMA10/RA10_12") (pintype "bidirectional"))
    )
    (net (code "56") (name "RB2") (class "Default")
      (node (ref "IC1") (pin "23") (pinfunction "AN4/C1IN-/RP2/CN6/RB2_23") (pintype "bidirectional"))
      (node (ref "U$118") (pin "1") (pinfunction "1_1") (pintype "bidirectional"))
      (node (ref "U$75") (pin "1") (pinfunction "1_1") (pintype "bidirectional"))
    )
    (net (code "57") (name "RB3") (class "Default")
      (node (ref "IC1") (pin "24") (pinfunction "AN5/C1IN+/RP3/CN7/RB3_24") (pintype "bidirectional"))
      (node (ref "SW2") (pin "3") (pinfunction "3_3") (pintype "passive"))
    )
    (net (code "58") (name "RB4") (class "Default")
      (node (ref "IC1") (pin "33") (pinfunction "SOSCI/RP4/CN1/RB4_33") (pintype "bidirectional"))
      (node (ref "SW2") (pin "4") (pinfunction "4_4") (pintype "passive"))
    )
    (net (code "59") (name "RB7") (class "Default")
      (node (ref "IC1") (pin "43") (pinfunction "INT0/RP7/CN23/PMD5/RB7_43") (pintype "bidirectional"))
      (node (ref "IC4") (pin "1") (pinfunction "1_1") (pintype "bidirectional"))
    )
    (net (code "60") (name "RB8") (class "Default")
      (node (ref "IC1") (pin "44") (pinfunction "SCL1/RP8/CN22/PMD4/RB8_44") (pintype "bidirectional"))
      (node (ref "U$117") (pin "1") (pinfunction "1_1") (pintype "bidirectional"))
      (node (ref "U$69") (pin "1") (pinfunction "1_1") (pintype "bidirectional"))
    )
    (net (code "61") (name "RB9") (class "Default")
      (node (ref "IC1") (pin "1") (pinfunction "SDA1/RP9/CN21/PMD3/RB9_1") (pintype "bidirectional"))
      (node (ref "SW2") (pin "16") (pinfunction "16_16") (pintype "passive"))
    )
    (net (code "62") (name "RB10") (class "Default")
      (node (ref "IC1") (pin "8") (pinfunction "PGED2/PWM1H3/RP10/CN16/PMD2/RB10_8") (pintype "bidirectional"))
      (node (ref "U$9") (pin "2") (pinfunction "2_2") (pintype "bidirectional"))
    )
    (net (code "63") (name "RB11") (class "Default")
      (node (ref "IC1") (pin "9") (pinfunction "PGEC2/PWM1L3/RP11/CN15/PMD1/RB11_9") (pintype "bidirectional"))
      (node (ref "U$9") (pin "3") (pinfunction "3_3") (pintype "bidirectional"))
    )
    (net (code "64") (name "RC0") (class "Default")
      (node (ref "IC1") (pin "25") (pinfunction "AN6/RP16/CN8/RC0_25") (pintype "bidirectional"))
      (node (ref "SW2") (pin "5") (pinfunction "5_5") (pintype "passive"))
    )
    (net (code "65") (name "RC1") (class "Default")
      (node (ref "IC1") (pin "26") (pinfunction "AN7/RP17/CN9/RC1_26") (pintype "bidirectional"))
      (node (ref "SW1") (pin "3") (pinfunction "P$3_3") (pintype "bidirectional"))
    )
    (net (code "66") (name "RC2") (class "Default")
      (node (ref "IC1") (pin "27") (pinfunction "AN8/CVREF/RP18/PMA2/CN10/RC2_27") (pintype "bidirectional"))
    )
    (net (code "67") (name "RC5") (class "Default")
      (node (ref "IC1") (pin "38") (pinfunction "RP21/CN26/PMA3/RC5_38") (pintype "bidirectional"))
    )
    (net (code "68") (name "RC8") (class "Default")
      (node (ref "IC1") (pin "4") (pinfunction "RP24/CN20/PMA5/RC8_4") (pintype "bidirectional"))
      (node (ref "U$9") (pin "8") (pinfunction "8_8") (pintype "bidirectional"))
    )
    (net (code "69") (name "RC9") (class "Default")
      (node (ref "IC1") (pin "5") (pinfunction "RP25/CN19/PMA6/RC9_5") (pintype "bidirectional"))
      (node (ref "U$9") (pin "9") (pinfunction "9_9") (pintype "bidirectional"))
    )
    (net (code "70") (name "VPP") (class "Default")
      (node (ref "$$U$13") (pin "4") (pinfunction "4_4") (pintype "input"))
      (node (ref "SW2") (pin "6") (pinfunction "6_6") (pintype "passive"))
    )
    (net (code "71") (name "unconnected-(IC3-VREF-Pad5)") (class "Default")
      (node (ref "IC3") (pin "5") (pinfunction "VREF_5") (pintype "bidirectional"))
    )
    (net (code "72") (name "unconnected-(IC_L_HIGH-Pad1)") (class "Default")
      (node (ref "IC_L_HIGH") (pin "1") (pinfunction "1_1") (pintype "bidirectional"))
    )
    (net (code "73") (name "unconnected-(IC_L_LOW-Pad1)") (class "Default")
      (node (ref "IC_L_LOW") (pin "1") (pinfunction "1_1") (pintype "bidirectional"))
    )
    (net (code "74") (name "unconnected-(IC_R_HIGH-Pad1)") (class "Default")
      (node (ref "IC_R_HIGH") (pin "1") (pinfunction "1_1") (pintype "bidirectional"))
    )
    (net (code "75") (name "unconnected-(IC_R_LOW-Pad1)") (class "Default")
      (node (ref "IC_R_LOW") (pin "1") (pinfunction "1_1") (pintype "bidirectional"))
    )
    (net (code "76") (name "unconnected-(SW1-P$1-Pad1)") (class "Default")
      (node (ref "SW1") (pin "1") (pinfunction "P$1_1") (pintype "bidirectional"))
    )
    (net (code "77") (name "unconnected-(U$116-Pad1)") (class "Default")
      (node (ref "U$116") (pin "1") (pinfunction "1_1") (pintype "passive"))
    )
  )
)
